# shiftregisters.net
KiCad netlist of a schematic drawn in EAGLE
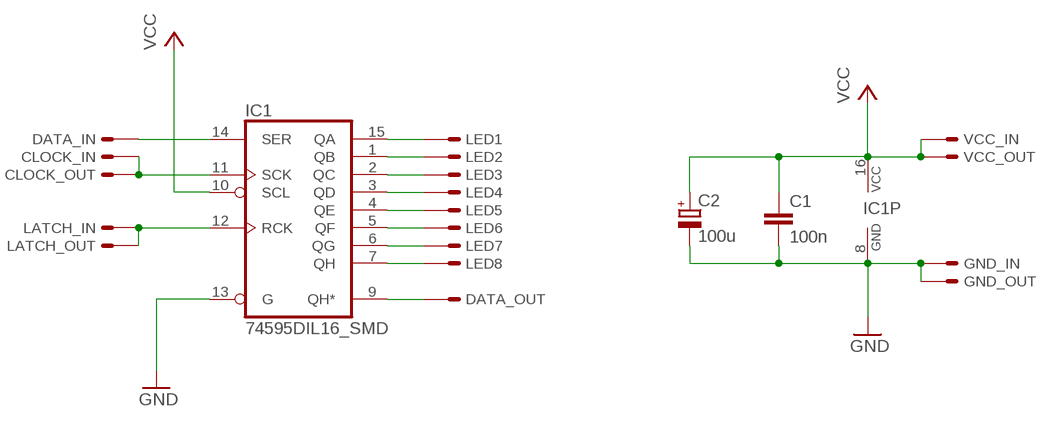
[diagram p0: schematic, sheet 1]

(export (version "E")
  (design (tool "Eeschema 10.0.6"))
  (components
    (comp (ref "C1")
      (value "100n")
      (footprint "eagle-import:C0805K")
      (libsource (lib "eagle-import") (part "C-EUC0805K"))
    )
    (comp (ref "C2")
      (value "100u")
      (footprint "eagle-import:E2,5-5-L-12SMD")
      (libsource (lib "eagle-import") (part "CPOL-EUE2.5-5-L-12-SMD"))
    )
    (comp (ref "CLOCK_IN")
      (value "PINS-1-1SMD")
      (footprint "eagle-import:SMD")
      (libsource (lib "eagle-import") (part "PINS-1-1SMD"))
    )
    (comp (ref "CLOCK_OUT")
      (value "PINS-1-1SMD")
      (footprint "eagle-import:SMD")
      (libsource (lib "eagle-import") (part "PINS-1-1SMD"))
    )
    (comp (ref "DATA_IN")
      (value "PINS-1-1SMD")
      (footprint "eagle-import:SMD")
      (libsource (lib "eagle-import") (part "PINS-1-1SMD"))
    )
    (comp (ref "DATA_OUT")
      (value "PINS-1-1SMD")
      (footprint "eagle-import:SMD")
      (libsource (lib "eagle-import") (part "PINS-1-1SMD"))
    )
    (comp (ref "GND_IN")
      (value "PINS-1-1SMD")
      (footprint "eagle-import:SMD")
      (libsource (lib "eagle-import") (part "PINS-1-1SMD"))
    )
    (comp (ref "GND_OUT")
      (value "PINS-1-1SMD")
      (footprint "eagle-import:SMD")
      (libsource (lib "eagle-import") (part "PINS-1-1SMD"))
    )
    (comp (ref "IC1")
      (value "74595DIL16_SMD")
      (footprint "eagle-import:DIL16_SMD")
      (libsource (lib "eagle-import") (part "74595DIL16_SMD"))
    )
    (comp (ref "LATCH_IN")
      (value "PINS-1-1SMD")
      (footprint "eagle-import:SMD")
      (libsource (lib "eagle-import") (part "PINS-1-1SMD"))
    )
    (comp (ref "LATCH_OUT")
      (value "PINS-1-1SMD")
      (footprint "eagle-import:SMD")
      (libsource (lib "eagle-import") (part "PINS-1-1SMD"))
    )
    (comp (ref "LED1")
      (value "PINS-1-1SMD")
      (footprint "eagle-import:SMD")
      (libsource (lib "eagle-import") (part "PINS-1-1SMD"))
    )
    (comp (ref "LED2")
      (value "PINS-1-1SMD")
      (footprint "eagle-import:SMD")
      (libsource (lib "eagle-import") (part "PINS-1-1SMD"))
    )
    (comp (ref "LED3")
      (value "PINS-1-1SMD")
      (footprint "eagle-import:SMD")
      (libsource (lib "eagle-import") (part "PINS-1-1SMD"))
    )
    (comp (ref "LED4")
      (value "PINS-1-1SMD")
      (footprint "eagle-import:SMD")
      (libsource (lib "eagle-import") (part "PINS-1-1SMD"))
    )
    (comp (ref "LED5")
      (value "PINS-1-1SMD")
      (footprint "eagle-import:SMD")
      (libsource (lib "eagle-import") (part "PINS-1-1SMD"))
    )
    (comp (ref "LED6")
      (value "PINS-1-1SMD")
      (footprint "eagle-import:SMD")
      (libsource (lib "eagle-import") (part "PINS-1-1SMD"))
    )
    (comp (ref "LED7")
      (value "PINS-1-1SMD")
      (footprint "eagle-import:SMD")
      (libsource (lib "eagle-import") (part "PINS-1-1SMD"))
    )
    (comp (ref "LED8")
      (value "PINS-1-1SMD")
      (footprint "eagle-import:SMD")
      (libsource (lib "eagle-import") (part "PINS-1-1SMD"))
    )
    (comp (ref "VCC_IN")
      (value "PINS-1-1SMD")
      (footprint "eagle-import:SMD")
      (libsource (lib "eagle-import") (part "PINS-1-1SMD"))
    )
    (comp (ref "VCC_OUT")
      (value "PINS-1-1SMD")
      (footprint "eagle-import:SMD")
      (libsource (lib "eagle-import") (part "PINS-1-1SMD"))
    )
  )
  (nets
    (net (code "1") (name "GND") (class "Default")
      (node (ref "C1") (pin "2") (pinfunction "2_2") (pintype "passive"))
      (node (ref "C2") (pin "-") (pinfunction "-_-") (pintype "passive"))
      (node (ref "GND_IN") (pin "1") (pinfunction "S_1") (pintype "passive"))
      (node (ref "GND_OUT") (pin "1") (pinfunction "S_1") (pintype "passive"))
      (node (ref "IC1") (pin "13") (pinfunction "G_13") (pintype "input"))
      (node (ref "IC1") (pin "8") (pinfunction "GND_8") (pintype "power_in"))
    )
    (net (code "2") (name "Net-(CLOCK_IN-S)") (class "Default")
      (node (ref "CLOCK_IN") (pin "1") (pinfunction "S_1") (pintype "passive"))
      (node (ref "CLOCK_OUT") (pin "1") (pinfunction "S_1") (pintype "passive"))
      (node (ref "IC1") (pin "11") (pinfunction "SCK_11") (pintype "input"))
    )
    (net (code "3") (name "Net-(DATA_IN-S)") (class "Default")
      (node (ref "DATA_IN") (pin "1") (pinfunction "S_1") (pintype "passive"))
      (node (ref "IC1") (pin "14") (pinfunction "SER_14") (pintype "input"))
    )
    (net (code "4") (name "Net-(DATA_OUT-S)") (class "Default")
      (node (ref "DATA_OUT") (pin "1") (pinfunction "S_1") (pintype "passive"))
      (node (ref "IC1") (pin "9") (pinfunction "QH*_9") (pintype "tri_state"))
    )
    (net (code "5") (name "Net-(IC1A-QA)") (class "Default")
      (node (ref "IC1") (pin "15") (pinfunction "QA_15") (pintype "tri_state"))
      (node (ref "LED1") (pin "1") (pinfunction "S_1") (pintype "passive"))
    )
    (net (code "6") (name "Net-(IC1A-QB)") (class "Default")
      (node (ref "IC1") (pin "1") (pinfunction "QB_1") (pintype "tri_state"))
      (node (ref "LED2") (pin "1") (pinfunction "S_1") (pintype "passive"))
    )
    (net (code "7") (name "Net-(IC1A-QC)") (class "Default")
      (node (ref "IC1") (pin "2") (pinfunction "QC_2") (pintype "tri_state"))
      (node (ref "LED3") (pin "1") (pinfunction "S_1") (pintype "passive"))
    )
    (net (code "8") (name "Net-(IC1A-QD)") (class "Default")
      (node (ref "IC1") (pin "3") (pinfunction "QD_3") (pintype "tri_state"))
      (node (ref "LED4") (pin "1") (pinfunction "S_1") (pintype "passive"))
    )
    (net (code "9") (name "Net-(IC1A-QE)") (class "Default")
      (node (ref "IC1") (pin "4") (pinfunction "QE_4") (pintype "tri_state"))
      (node (ref "LED5") (pin "1") (pinfunction "S_1") (pintype "passive"))
    )
    (net (code "10") (name "Net-(IC1A-QF)") (class "Default")
      (node (ref "IC1") (pin "5") (pinfunction "QF_5") (pintype "tri_state"))
      (node (ref "LED6") (pin "1") (pinfunction "S_1") (pintype "passive"))
    )
    (net (code "11") (name "Net-(IC1A-QG)") (class "Default")
      (node (ref "IC1") (pin "6") (pinfunction "QG_6") (pintype "tri_state"))
      (node (ref "LED7") (pin "1") (pinfunction "S_1") (pintype "passive"))
    )
    (net (code "12") (name "Net-(IC1A-QH)") (class "Default")
      (node (ref "IC1") (pin "7") (pinfunction "QH_7") (pintype "tri_state"))
      (node (ref "LED8") (pin "1") (pinfunction "S_1") (pintype "passive"))
    )
    (net (code "13") (name "Net-(IC1A-RCK)") (class "Default")
      (node (ref "IC1") (pin "12") (pinfunction "RCK_12") (pintype "input"))
      (node (ref "LATCH_IN") (pin "1") (pinfunction "S_1") (pintype "passive"))
      (node (ref "LATCH_OUT") (pin "1") (pinfunction "S_1") (pintype "passive"))
    )
    (net (code "14") (name "VCC") (class "Default")
      (node (ref "C1") (pin "1") (pinfunction "1_1") (pintype "passive"))
      (node (ref "C2") (pin "+") (pinfunction "+_+") (pintype "passive"))
      (node (ref "IC1") (pin "10") (pinfunction "SCL_10") (pintype "input"))
      (node (ref "IC1") (pin "16") (pinfunction "VCC_16") (pintype "power_in"))
      (node (ref "VCC_IN") (pin "1") (pinfunction "S_1") (pintype "passive"))
      (node (ref "VCC_OUT") (pin "1") (pinfunction "S_1") (pintype "passive"))
    )
  )
)
